# Sensor_Board.net
KiCad netlist of a schematic drawn in Altium Designer
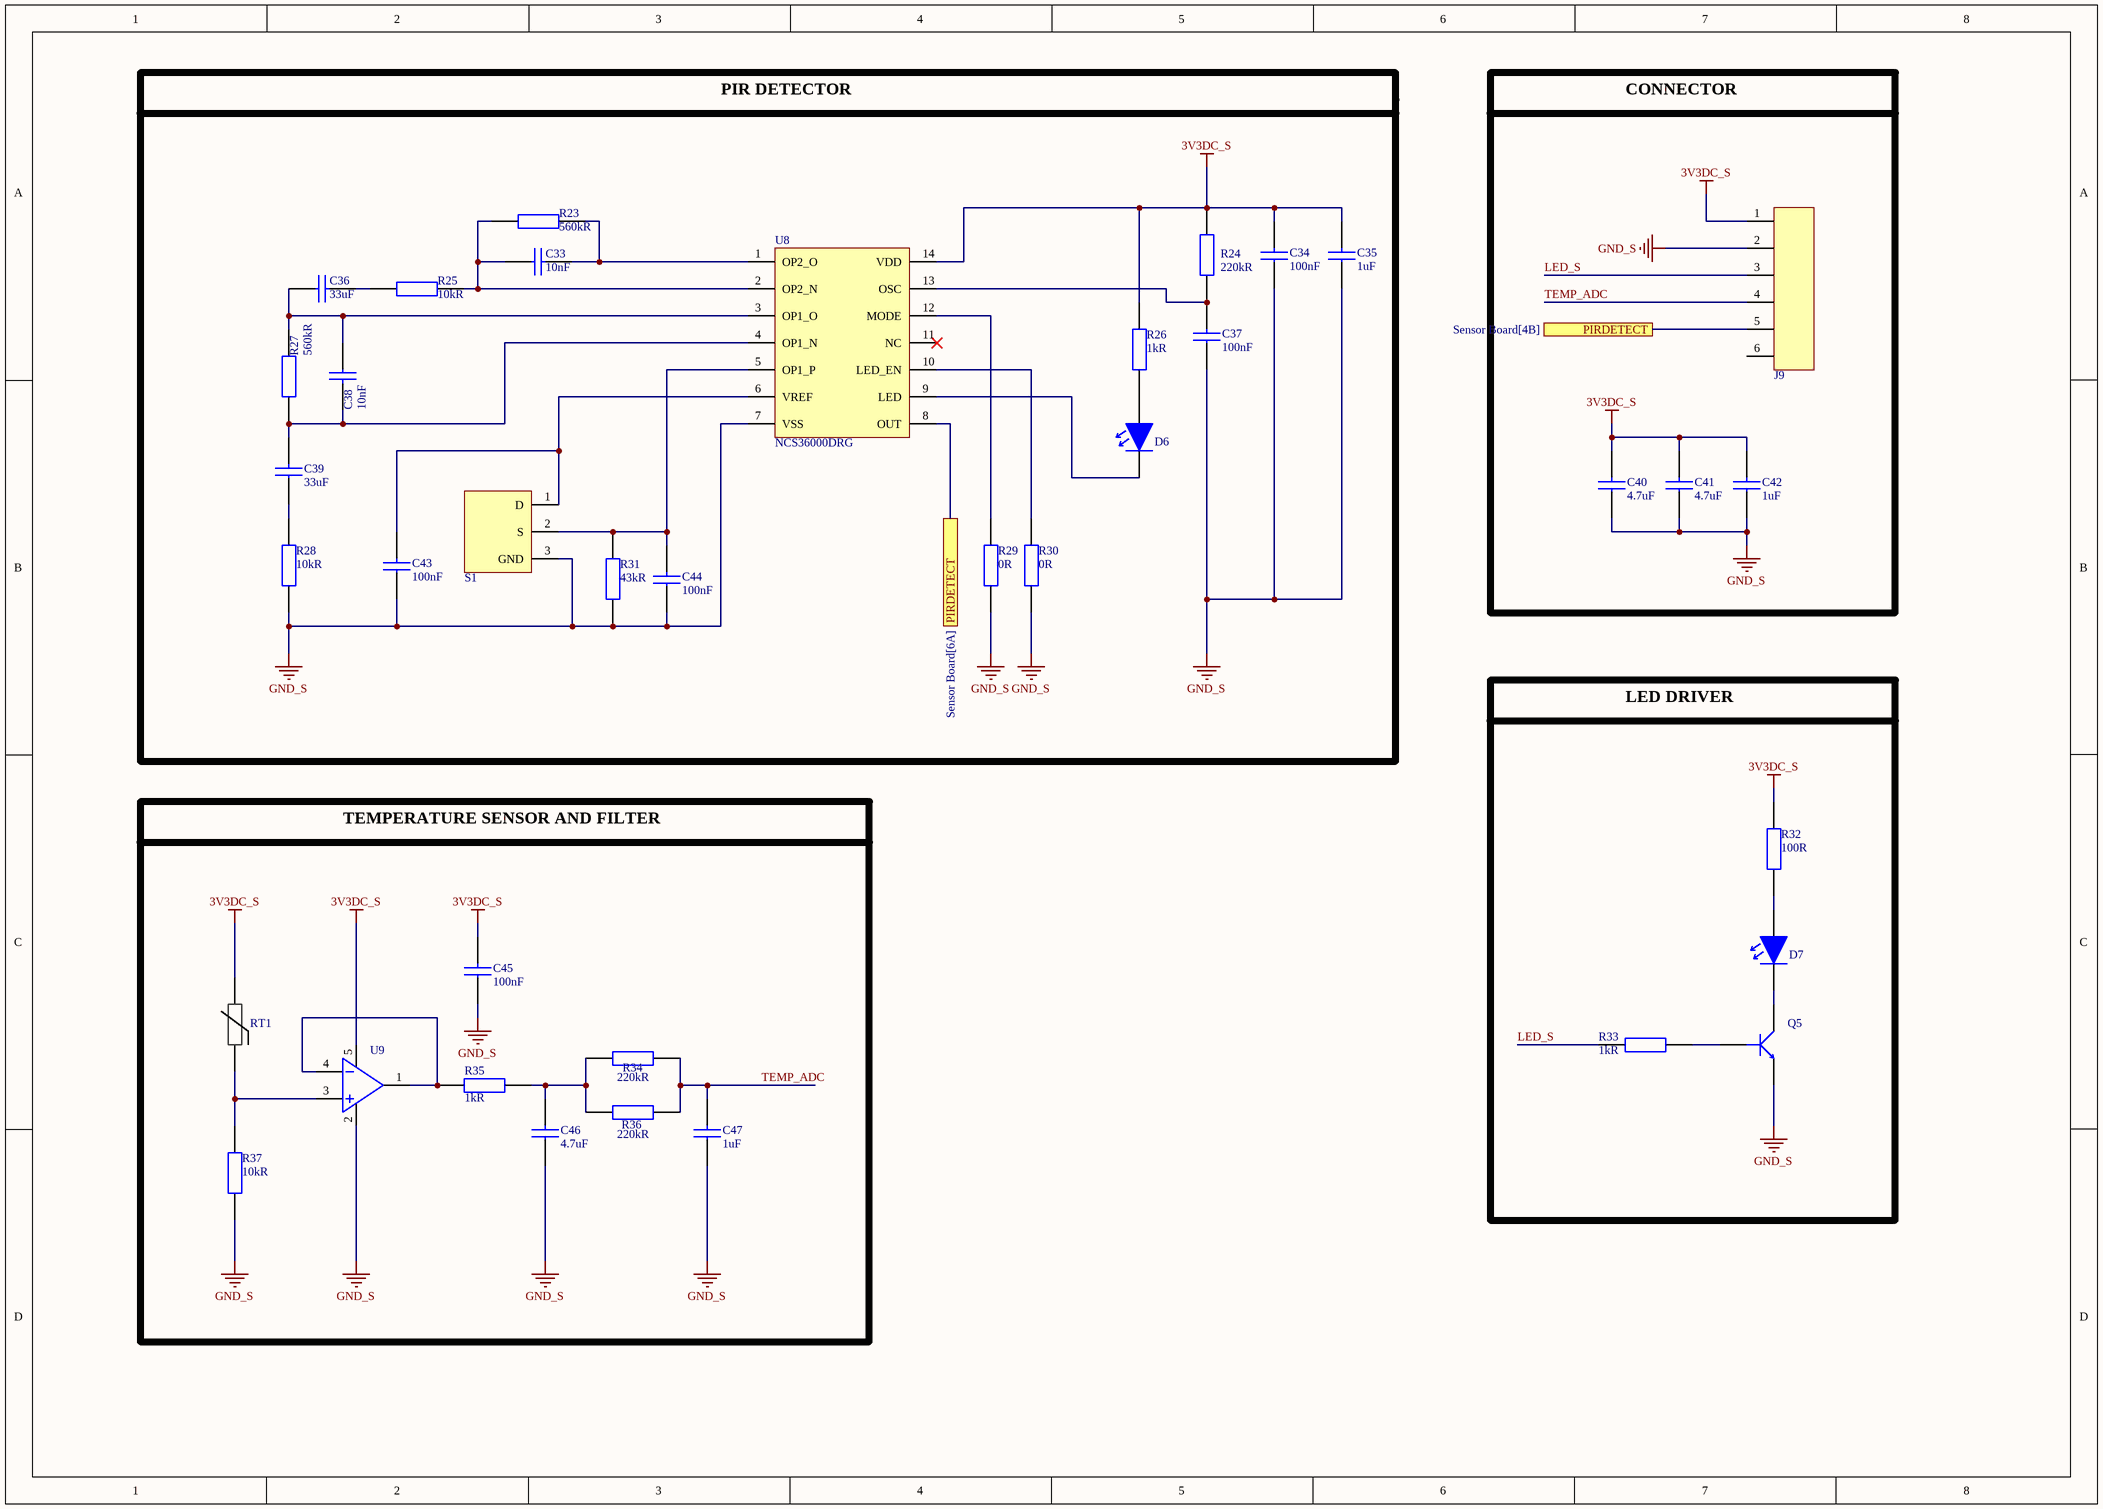
[diagram p0: Sensor Board.SchDoc]

(export (version "E")
  (design (tool "Eeschema 10.0.6"))
  (components
    (comp (ref "C33")
      (value "0603B103K160CT")
      (footprint "CAP_0603")
      (description "CAP CER 10nF %10 0603")
      (fields
        (field (name "MANUFACTURER") "Walsin Technologies")
        (field (name "TOLERANCE") "10%")
        (field (name "CAPACITANCE") "10nF")
        (field (name "DESIGNED BY") "BERK")
      )
      (libsource (lib "UDEMY_Library") (part "CAP CER 10nF 0603"))
    )
    (comp (ref "C34")
      (value "C0603C104K5RACTU")
      (footprint "CAP_0603")
      (description "CAP CER 100nF %10 0603 SMD")
      (fields
        (field (name "MANUFACTURER") "KEMET")
        (field (name "TOLERANCE") "10%")
        (field (name "CAPACITANCE") "100nF")
        (field (name "DESIGNED BY") "BERK")
      )
      (libsource (lib "UDEMY_Library") (part "CAP CER 100nF 0603"))
    )
    (comp (ref "C35")
      (value "CL21B105KBFNNNE")
      (footprint "CAP_0805")
      (description "CAP CER 1uF %10 0805")
      (fields
        (field (name "MANUFACTURER") "Samsung")
        (field (name "TOLERANCE") "10%")
        (field (name "CAPACITANCE") "1uF")
        (field (name "DESIGNED BY") "BERK")
      )
      (libsource (lib "UDEMY_Library") (part "CAP CER 1uF 0805"))
    )
    (comp (ref "C36")
      (value "C3216X5R1E336M160AC")
      (footprint "CAP_1206")
      (description "CAP CER 33uF %20 1206 SMD")
      (fields
        (field (name "MANUFACTURER") "TDK")
        (field (name "TOLERANCE") "20%")
        (field (name "CAPACITANCE") "33uF")
        (field (name "DESIGNED BY") "BERK")
      )
      (libsource (lib "UDEMY_Library") (part "CAP CER 33uF 1206"))
    )
    (comp (ref "C37")
      (value "C0603C104K5RACTU")
      (footprint "CAP_0603")
      (description "CAP CER 100nF %10 0603 SMD")
      (fields
        (field (name "MANUFACTURER") "KEMET")
        (field (name "TOLERANCE") "10%")
        (field (name "CAPACITANCE") "100nF")
        (field (name "DESIGNED BY") "BERK")
      )
      (libsource (lib "UDEMY_Library") (part "CAP CER 100nF 0603"))
    )
    (comp (ref "C38")
      (value "0603B103K160CT")
      (footprint "CAP_0603")
      (description "CAP CER 10nF %10 0603")
      (fields
        (field (name "MANUFACTURER") "Walsin Technologies")
        (field (name "TOLERANCE") "10%")
        (field (name "CAPACITANCE") "10nF")
        (field (name "DESIGNED BY") "BERK")
      )
      (libsource (lib "UDEMY_Library") (part "CAP CER 10nF 0603"))
    )
    (comp (ref "C39")
      (value "C3216X5R1E336M160AC")
      (footprint "CAP_1206")
      (description "CAP CER 33uF %20 1206 SMD")
      (fields
        (field (name "MANUFACTURER") "TDK")
        (field (name "TOLERANCE") "20%")
        (field (name "CAPACITANCE") "33uF")
        (field (name "DESIGNED BY") "BERK")
      )
      (libsource (lib "UDEMY_Library") (part "CAP CER 33uF 1206"))
    )
    (comp (ref "C40")
      (value "CL21A475KAQNNNE")
      (footprint "CAP_0805")
      (description "CAP CER 4.7uF %10 0805")
      (fields
        (field (name "MANUFACTURER") "Samsung")
        (field (name "TOLERANCE") "10%")
        (field (name "CAPACITANCE") "4.7uF")
        (field (name "DESIGNED BY") "BERK")
      )
      (libsource (lib "UDEMY_Library") (part "CAP CER 4.7uF 0805"))
    )
    (comp (ref "C41")
      (value "CL21A475KAQNNNE")
      (footprint "CAP_0805")
      (description "CAP CER 4.7uF %10 0805")
      (fields
        (field (name "MANUFACTURER") "Samsung")
        (field (name "TOLERANCE") "10%")
        (field (name "CAPACITANCE") "4.7uF")
        (field (name "DESIGNED BY") "BERK")
      )
      (libsource (lib "UDEMY_Library") (part "CAP CER 4.7uF 0805"))
    )
    (comp (ref "C42")
      (value "CL21B105KBFNNNE")
      (footprint "CAP_0805")
      (description "CAP CER 1uF %10 0805")
      (fields
        (field (name "MANUFACTURER") "Samsung")
        (field (name "TOLERANCE") "10%")
        (field (name "CAPACITANCE") "1uF")
        (field (name "DESIGNED BY") "BERK")
      )
      (libsource (lib "UDEMY_Library") (part "CAP CER 1uF 0805"))
    )
    (comp (ref "C43")
      (value "C0603C104K5RACTU")
      (footprint "CAP_0603")
      (description "CAP CER 100nF %10 0603 SMD")
      (fields
        (field (name "MANUFACTURER") "KEMET")
        (field (name "TOLERANCE") "10%")
        (field (name "CAPACITANCE") "100nF")
        (field (name "DESIGNED BY") "BERK")
      )
      (libsource (lib "UDEMY_Library") (part "CAP CER 100nF 0603"))
    )
    (comp (ref "C44")
      (value "C0603C104K5RACTU")
      (footprint "CAP_0603")
      (description "CAP CER 100nF %10 0603 SMD")
      (fields
        (field (name "MANUFACTURER") "KEMET")
        (field (name "TOLERANCE") "10%")
        (field (name "CAPACITANCE") "100nF")
        (field (name "DESIGNED BY") "BERK")
      )
      (libsource (lib "UDEMY_Library") (part "CAP CER 100nF 0603"))
    )
    (comp (ref "C45")
      (value "C0603C104K5RACTU")
      (footprint "CAP_0603")
      (description "CAP CER 100nF %10 0603 SMD")
      (fields
        (field (name "MANUFACTURER") "KEMET")
        (field (name "TOLERANCE") "10%")
        (field (name "CAPACITANCE") "100nF")
        (field (name "DESIGNED BY") "BERK")
      )
      (libsource (lib "UDEMY_Library") (part "CAP CER 100nF 0603"))
    )
    (comp (ref "C46")
      (value "CL21A475KAQNNNE")
      (footprint "CAP_0805")
      (description "CAP CER 4.7uF %10 0805")
      (fields
        (field (name "MANUFACTURER") "Samsung")
        (field (name "TOLERANCE") "10%")
        (field (name "CAPACITANCE") "4.7uF")
        (field (name "DESIGNED BY") "BERK")
      )
      (libsource (lib "UDEMY_Library") (part "CAP CER 4.7uF 0805"))
    )
    (comp (ref "C47")
      (value "CL21B105KBFNNNE")
      (footprint "CAP_0805")
      (description "CAP CER 1uF %10 0805")
      (fields
        (field (name "MANUFACTURER") "Samsung")
        (field (name "TOLERANCE") "10%")
        (field (name "CAPACITANCE") "1uF")
        (field (name "DESIGNED BY") "BERK")
      )
      (libsource (lib "UDEMY_Library") (part "CAP CER 1uF 0805"))
    )
    (comp (ref "D6")
      (value "LTST-C171GKT")
      (footprint "LED_GREEN_0805")
      (description "Green 0805 130 º Min 5 mcd Typical 12 mcd Water Clear Lens SMT LED")
      (fields (field (name "MANUFACTURER") "Vishay Lite-On") (field (name "DESIGNED BY") "BERK"))
      (libsource (lib "UDEMY_Library") (part "LED GREEN 0805"))
    )
    (comp (ref "D7")
      (value "LH R974-LP-1")
      (footprint "LED_RED_0805")
      (description "LED Uni-Color Hyper Red 660nm 2-Pin Chip 0805(2012Metric) T/R")
      (fields (field (name "MANUFACTURER") "Osram Opto") (field (name "DESIGNED BY") "BERK"))
      (libsource (lib "UDEMY_Library") (part "LED RED 0805"))
    )
    (comp (ref "J9")
      (value "64800611622")
      (footprint "64800611622")
      (description "1.50mm 6PIN Connector")
      (fields (field (name "MANUFACTURER") "Wurth Electronics"))
      (libsource (lib "UDEMY_Library") (part "64800611622_conn_6pin"))
    )
    (comp (ref "Q5")
      (value "MMBT3904-7-F")
      (footprint "SOT-23F")
      (description "Transistor General Purpose BJT NPN 40 Volt 0.2A Automotive 3-Pin SOT-23")
      (fields (field (name "MANUFACTURER") "Diodes Zetex") (field (name "DESIGNED BY") "BERK"))
      (libsource (lib "UDEMY_Library") (part "MMBT3904-7-F"))
    )
    (comp (ref "R23")
      (value "RC0603JR-07560KL")
      (footprint "RES_0603")
      (description "RES SMD 560K OHM 5% 1/10W 0603")
      (fields
        (field (name "MANUFACTURER") "Yageo")
        (field (name "TOLERANCE") "5%")
        (field (name "RESISTANCE") "560kR")
        (field (name "DESIGNED BY") "BERK")
      )
      (libsource (lib "UDEMY_Library") (part "RES 560K OHM 0603"))
    )
    (comp (ref "R24")
      (value "RC0603JR-07220KL")
      (footprint "RES_0603")
      (description "RES 220K %5 OHM 0603 SMD")
      (fields
        (field (name "MANUFACTURER") "Yageo")
        (field (name "TOLERANCE") "5%")
        (field (name "RESISTANCE") "220kR")
      )
      (libsource (lib "UDEMY_Library") (part "RES 220K OHM 0603"))
    )
    (comp (ref "R25")
      (value "RC0603FR-0710KL")
      (footprint "RES_0603")
      (description "RES 10K %1 OHM 0603 SMD")
      (fields
        (field (name "MANUFACTURER") "Yageo")
        (field (name "TOLERANCE") "1%")
        (field (name "RESISTANCE") "10kR")
        (field (name "DESIGNED BY") "BERK")
      )
      (libsource (lib "") (part "RES 10K OHM 0603_1"))
    )
    (comp (ref "R26")
      (value "RC0603FR-0710KL")
      (footprint "RES_0603")
      (description "RES 1K %1 OHM 0603 SMD")
      (fields
        (field (name "MANUFACTURER") "Yageo")
        (field (name "MANUFACTURER PART NUMBER") "RC0603JR-071KL")
        (field (name "RESISTANCE") "1kR")
        (field (name "DESIGNED BY") "BERK")
      )
      (libsource (lib "") (part "RES 1K OHM 0603_1"))
    )
    (comp (ref "R27")
      (value "RC0603JR-07560KL")
      (footprint "RES_0603")
      (description "RES SMD 560K OHM 5% 1/10W 0603")
      (fields
        (field (name "MANUFACTURER") "Yageo")
        (field (name "TOLERANCE") "5%")
        (field (name "RESISTANCE") "560kR")
        (field (name "DESIGNED BY") "BERK")
      )
      (libsource (lib "") (part "RES 560K OHM 0603_1"))
    )
    (comp (ref "R28")
      (value "RC0603FR-0710KL")
      (footprint "RES_0603")
      (description "RES 10K %1 OHM 0603 SMD")
      (fields
        (field (name "MANUFACTURER") "Yageo")
        (field (name "TOLERANCE") "1%")
        (field (name "RESISTANCE") "10kR")
        (field (name "DESIGNED BY") "BERK")
      )
      (libsource (lib "UDEMY_Library") (part "RES 10K OHM 0603"))
    )
    (comp (ref "R29")
      (value "RC0603JR-070RL")
      (footprint "RES_0603")
      (description "RES 0 %1 OHM 0603 SMD")
      (fields
        (field (name "MANUFACTURER") "Yageo")
        (field (name "TOLERANCE") "1%")
        (field (name "RESISTANCE") "0R")
        (field (name "DESIGNED BY") "BERK")
      )
      (libsource (lib "UDEMY_Library") (part "RES 0 OHM 0603"))
    )
    (comp (ref "R30")
      (value "RC0603JR-070RL")
      (footprint "RES_0603")
      (description "RES 0 %1 OHM 0603 SMD")
      (fields
        (field (name "MANUFACTURER") "Yageo")
        (field (name "TOLERANCE") "1%")
        (field (name "RESISTANCE") "0R")
        (field (name "DESIGNED BY") "BERK")
      )
      (libsource (lib "UDEMY_Library") (part "RES 0 OHM 0603"))
    )
    (comp (ref "R31")
      (value "RC0603JR-0743KL")
      (footprint "RES_0603")
      (description "RES 43K %5 OHM 0603 SMD")
      (fields
        (field (name "MANUFACTURER") "Yageo")
        (field (name "TOLERANCE") "5%")
        (field (name "RESISTANCE") "43kR")
        (field (name "DESIGNED BY") "BERK")
      )
      (libsource (lib "UDEMY_Library") (part "RES 43K OHM 0603"))
    )
    (comp (ref "R32")
      (value "RC0603JR-07100RL")
      (footprint "RES_0603")
      (description "RES 100 %5 OHM 0603 SMD")
      (fields
        (field (name "MANUFACTURER") "Yageo")
        (field (name "TOLERANCE") "5%")
        (field (name "RESISTANCE") "100R")
        (field (name "DESIGNED BY") "BERK")
      )
      (libsource (lib "UDEMY_Library") (part "RES 100 OHM 0603"))
    )
    (comp (ref "R33")
      (value "RC0603FR-0710KL")
      (footprint "RES_0603")
      (description "RES 1K %1 OHM 0603 SMD")
      (fields
        (field (name "MANUFACTURER") "Yageo")
        (field (name "MANUFACTURER PART NUMBER") "RC0603JR-071KL")
        (field (name "RESISTANCE") "1kR")
        (field (name "DESIGNED BY") "BERK")
      )
      (libsource (lib "UDEMY_Library") (part "RES 1K OHM 0603"))
    )
    (comp (ref "R34")
      (value "RC0603JR-07220KL")
      (footprint "RES_0603")
      (description "RES 220K %5 OHM 0603 SMD")
      (fields
        (field (name "MANUFACTURER") "Yageo")
        (field (name "TOLERANCE") "5%")
        (field (name "RESISTANCE") "220kR")
      )
      (libsource (lib "") (part "RES 220K OHM 0603_1"))
    )
    (comp (ref "R35")
      (value "RC0603FR-0710KL")
      (footprint "RES_0603")
      (description "RES 1K %1 OHM 0603 SMD")
      (fields
        (field (name "MANUFACTURER") "Yageo")
        (field (name "MANUFACTURER PART NUMBER") "RC0603JR-071KL")
        (field (name "RESISTANCE") "1kR")
        (field (name "DESIGNED BY") "BERK")
      )
      (libsource (lib "UDEMY_Library") (part "RES 1K OHM 0603"))
    )
    (comp (ref "R36")
      (value "RC0603JR-07220KL")
      (footprint "RES_0603")
      (description "RES 220K %5 OHM 0603 SMD")
      (fields
        (field (name "MANUFACTURER") "Yageo")
        (field (name "TOLERANCE") "5%")
        (field (name "RESISTANCE") "220kR")
      )
      (libsource (lib "") (part "RES 220K OHM 0603_1"))
    )
    (comp (ref "R37")
      (value "RC0603FR-0710KL")
      (footprint "RES_0603")
      (description "RES 10K %1 OHM 0603 SMD")
      (fields
        (field (name "MANUFACTURER") "Yageo")
        (field (name "TOLERANCE") "1%")
        (field (name "RESISTANCE") "10kR")
        (field (name "DESIGNED BY") "BERK")
      )
      (libsource (lib "UDEMY_Library") (part "RES 10K OHM 0603"))
    )
    (comp (ref "RT1")
      (value "TFPT1206L1002FM")
      (footprint "RES_1206")
      (description "Thermistor PTC 10K Ohm 1% 1206")
      (fields
        (field (name "MANUFACTURER") "Vishay Dale")
        (field (name "TOLERANCE") "1%")
        (field (name "DESIGNED BY") "BERK")
      )
      (libsource (lib "UDEMY_Library") (part "TFPT1206L1002FM"))
    )
    (comp (ref "S1")
      (value "LHI 878/3902")
      (footprint "LHI 878")
      (description "SENSOR PYRO DETECTOR DUAL MOTION")
      (fields (field (name "DESIGNED BY") "BERK"))
      (libsource (lib "UDEMY_Library") (part "LHI 878/3902"))
    )
    (comp (ref "U8")
      (value "NCS36000DRG")
      (footprint "SOIC14")
      (description "PIR Controller Low Noise Amplifiers and LDO Regulator 14-Pin SOIC N T/R")
      (fields (field (name "MANUFACTURER") "ON Semiconductor") (field (name "DESIGNED BY") "BERK"))
      (libsource (lib "UDEMY_Library") (part "NCS36000"))
    )
    (comp (ref "U9")
      (value "OPA314AIDBVR")
      (footprint "SOT23-5")
      (description "Op Amp OPA314")
      (fields (field (name "MANUFACTURER") "Texas Instruments") (field (name "DESIGNED BY") "BERK"))
      (libsource (lib "UDEMY_Library") (part "OPA314"))
    )
  )
  (nets
    (net (code "1") (name "/LED_S") (class "Default")
      (node (ref "J9") (pin "3") (pintype "power_in"))
      (node (ref "R33") (pin "1") (pinfunction "1_1") (pintype "passive"))
    )
    (net (code "2") (name "/PIRDETECT") (class "Default")
      (node (ref "J9") (pin "5") (pintype "power_in"))
      (node (ref "U8") (pin "8") (pinfunction "OUT_8") (pintype "passive"))
    )
    (net (code "3") (name "/TEMP_ADC") (class "Default")
      (node (ref "C47") (pin "2") (pinfunction "2_2") (pintype "passive"))
      (node (ref "J9") (pin "4") (pintype "power_in"))
      (node (ref "R34") (pin "2") (pinfunction "2_2") (pintype "passive"))
      (node (ref "R36") (pin "2") (pinfunction "2_2") (pintype "passive"))
    )
    (net (code "4") (name "3V3DC_S") (class "Default")
      (node (ref "C34") (pin "2") (pinfunction "2_2") (pintype "passive"))
      (node (ref "C35") (pin "2") (pinfunction "2_2") (pintype "passive"))
      (node (ref "C40") (pin "2") (pinfunction "2_2") (pintype "passive"))
      (node (ref "C41") (pin "2") (pinfunction "2_2") (pintype "passive"))
      (node (ref "C42") (pin "2") (pinfunction "2_2") (pintype "passive"))
      (node (ref "C45") (pin "2") (pinfunction "2_2") (pintype "passive"))
      (node (ref "J9") (pin "1") (pintype "power_in"))
      (node (ref "R24") (pin "2") (pinfunction "2_2") (pintype "passive"))
      (node (ref "R26") (pin "2") (pinfunction "2_2") (pintype "passive"))
      (node (ref "R32") (pin "2") (pinfunction "2_2") (pintype "passive"))
      (node (ref "RT1") (pin "2") (pinfunction "2_2") (pintype "passive"))
      (node (ref "U8") (pin "14") (pinfunction "VDD_14") (pintype "passive"))
      (node (ref "U9") (pin "5") (pinfunction "5_5") (pintype "passive"))
    )
    (net (code "5") (name "GND_S") (class "Default")
      (node (ref "C34") (pin "1") (pinfunction "1_1") (pintype "passive"))
      (node (ref "C35") (pin "1") (pinfunction "1_1") (pintype "passive"))
      (node (ref "C37") (pin "1") (pinfunction "1_1") (pintype "passive"))
      (node (ref "C40") (pin "1") (pinfunction "1_1") (pintype "passive"))
      (node (ref "C41") (pin "1") (pinfunction "1_1") (pintype "passive"))
      (node (ref "C42") (pin "1") (pinfunction "1_1") (pintype "passive"))
      (node (ref "C43") (pin "1") (pinfunction "1_1") (pintype "passive"))
      (node (ref "C44") (pin "1") (pinfunction "1_1") (pintype "passive"))
      (node (ref "C45") (pin "1") (pinfunction "1_1") (pintype "passive"))
      (node (ref "C46") (pin "1") (pinfunction "1_1") (pintype "passive"))
      (node (ref "C47") (pin "1") (pinfunction "1_1") (pintype "passive"))
      (node (ref "J9") (pin "2") (pintype "power_in"))
      (node (ref "Q5") (pin "2") (pinfunction "E_2") (pintype "power_in"))
      (node (ref "R28") (pin "1") (pinfunction "1_1") (pintype "passive"))
      (node (ref "R29") (pin "1") (pinfunction "1_1") (pintype "passive"))
      (node (ref "R30") (pin "1") (pinfunction "1_1") (pintype "passive"))
      (node (ref "R31") (pin "1") (pinfunction "1_1") (pintype "passive"))
      (node (ref "R37") (pin "1") (pinfunction "1_1") (pintype "passive"))
      (node (ref "S1") (pin "3") (pinfunction "GND_3") (pintype "passive"))
      (node (ref "U8") (pin "7") (pinfunction "VSS_7") (pintype "passive"))
      (node (ref "U9") (pin "2") (pinfunction "2_2") (pintype "passive"))
    )
    (net (code "6") (name "Net-(C36-Pad2)") (class "Default")
      (node (ref "C36") (pin "2") (pinfunction "2_2") (pintype "passive"))
      (node (ref "R25") (pin "1") (pinfunction "1_1") (pintype "passive"))
    )
    (net (code "7") (name "Net-(C39-Pad1)") (class "Default")
      (node (ref "C39") (pin "1") (pinfunction "1_1") (pintype "passive"))
      (node (ref "R28") (pin "2") (pinfunction "2_2") (pintype "passive"))
    )
    (net (code "8") (name "Net-(C46-Pad2)") (class "Default")
      (node (ref "C46") (pin "2") (pinfunction "2_2") (pintype "passive"))
      (node (ref "R34") (pin "1") (pinfunction "1_1") (pintype "passive"))
      (node (ref "R35") (pin "2") (pinfunction "2_2") (pintype "passive"))
      (node (ref "R36") (pin "1") (pinfunction "1_1") (pintype "passive"))
    )
    (net (code "9") (name "Net-(D6-Pad2)") (class "Default")
      (node (ref "D6") (pin "2") (pinfunction "2_2") (pintype "power_in"))
      (node (ref "R26") (pin "1") (pinfunction "1_1") (pintype "passive"))
    )
    (net (code "10") (name "Net-(D7-Pad2)") (class "Default")
      (node (ref "D7") (pin "2") (pinfunction "2_2") (pintype "power_in"))
      (node (ref "R32") (pin "1") (pinfunction "1_1") (pintype "passive"))
    )
    (net (code "11") (name "Net-(Q5-B)") (class "Default")
      (node (ref "Q5") (pin "1") (pinfunction "B_1") (pintype "power_in"))
      (node (ref "R33") (pin "2") (pinfunction "2_2") (pintype "passive"))
    )
    (net (code "12") (name "Net-(Q5-C)") (class "Default")
      (node (ref "D7") (pin "1") (pinfunction "1_1") (pintype "power_in"))
      (node (ref "Q5") (pin "3") (pinfunction "C_3") (pintype "power_in"))
    )
    (net (code "13") (name "Net-(R35-Pad1)") (class "Default")
      (node (ref "R35") (pin "1") (pinfunction "1_1") (pintype "passive"))
      (node (ref "U9") (pin "1") (pinfunction "1_1") (pintype "passive"))
      (node (ref "U9") (pin "4") (pinfunction "4_4") (pintype "passive"))
    )
    (net (code "14") (name "Net-(R37-Pad2)") (class "Default")
      (node (ref "R37") (pin "2") (pinfunction "2_2") (pintype "passive"))
      (node (ref "RT1") (pin "1") (pinfunction "1_1") (pintype "passive"))
      (node (ref "U9") (pin "3") (pinfunction "3_3") (pintype "passive"))
    )
    (net (code "15") (name "Net-(S1-D)") (class "Default")
      (node (ref "C43") (pin "2") (pinfunction "2_2") (pintype "passive"))
      (node (ref "S1") (pin "1") (pinfunction "D_1") (pintype "passive"))
      (node (ref "U8") (pin "6") (pinfunction "VREF_6") (pintype "passive"))
    )
    (net (code "16") (name "Net-(S1-S)") (class "Default")
      (node (ref "C44") (pin "2") (pinfunction "2_2") (pintype "passive"))
      (node (ref "R31") (pin "2") (pinfunction "2_2") (pintype "passive"))
      (node (ref "S1") (pin "2") (pinfunction "S_2") (pintype "passive"))
      (node (ref "U8") (pin "5") (pinfunction "OP1_P_5") (pintype "passive"))
    )
    (net (code "17") (name "Net-(U8-LED)") (class "Default")
      (node (ref "D6") (pin "1") (pinfunction "1_1") (pintype "power_in"))
      (node (ref "U8") (pin "9") (pinfunction "LED_9") (pintype "passive"))
    )
    (net (code "18") (name "Net-(U8-LED_EN)") (class "Default")
      (node (ref "R30") (pin "2") (pinfunction "2_2") (pintype "passive"))
      (node (ref "U8") (pin "10") (pinfunction "LED_EN_10") (pintype "passive"))
    )
    (net (code "19") (name "Net-(U8-MODE)") (class "Default")
      (node (ref "R29") (pin "2") (pinfunction "2_2") (pintype "passive"))
      (node (ref "U8") (pin "12") (pinfunction "MODE_12") (pintype "passive"))
    )
    (net (code "20") (name "Net-(U8-OP1_N)") (class "Default")
      (node (ref "C38") (pin "2") (pinfunction "2_2") (pintype "passive"))
      (node (ref "C39") (pin "2") (pinfunction "2_2") (pintype "passive"))
      (node (ref "R27") (pin "1") (pinfunction "1_1") (pintype "passive"))
      (node (ref "U8") (pin "4") (pinfunction "OP1_N_4") (pintype "passive"))
    )
    (net (code "21") (name "Net-(U8-OP1_O)") (class "Default")
      (node (ref "C36") (pin "1") (pinfunction "1_1") (pintype "passive"))
      (node (ref "C38") (pin "1") (pinfunction "1_1") (pintype "passive"))
      (node (ref "R27") (pin "2") (pinfunction "2_2") (pintype "passive"))
      (node (ref "U8") (pin "3") (pinfunction "OP1_O_3") (pintype "passive"))
    )
    (net (code "22") (name "Net-(U8-OP2_N)") (class "Default")
      (node (ref "C33") (pin "1") (pinfunction "1_1") (pintype "passive"))
      (node (ref "R23") (pin "1") (pinfunction "1_1") (pintype "passive"))
      (node (ref "R25") (pin "2") (pinfunction "2_2") (pintype "passive"))
      (node (ref "U8") (pin "2") (pinfunction "OP2_N_2") (pintype "passive"))
    )
    (net (code "23") (name "Net-(U8-OP2_O)") (class "Default")
      (node (ref "C33") (pin "2") (pinfunction "2_2") (pintype "passive"))
      (node (ref "R23") (pin "2") (pinfunction "2_2") (pintype "passive"))
      (node (ref "U8") (pin "1") (pinfunction "OP2_O_1") (pintype "passive"))
    )
    (net (code "24") (name "Net-(U8-OSC)") (class "Default")
      (node (ref "C37") (pin "2") (pinfunction "2_2") (pintype "passive"))
      (node (ref "R24") (pin "1") (pinfunction "1_1") (pintype "passive"))
      (node (ref "U8") (pin "13") (pinfunction "OSC_13") (pintype "passive"))
    )
    (net (code "25") (name "unconnected-(J9-Pad6)") (class "Default")
      (node (ref "J9") (pin "6") (pintype "power_in"))
    )
    (net (code "26") (name "unconnected-(U8-NC-Pad11)") (class "Default")
      (node (ref "U8") (pin "11") (pinfunction "NC_11") (pintype "passive+no_connect"))
    )
  )
)
